# ears_v40.net
KiCad netlist of a schematic drawn in EAGLE
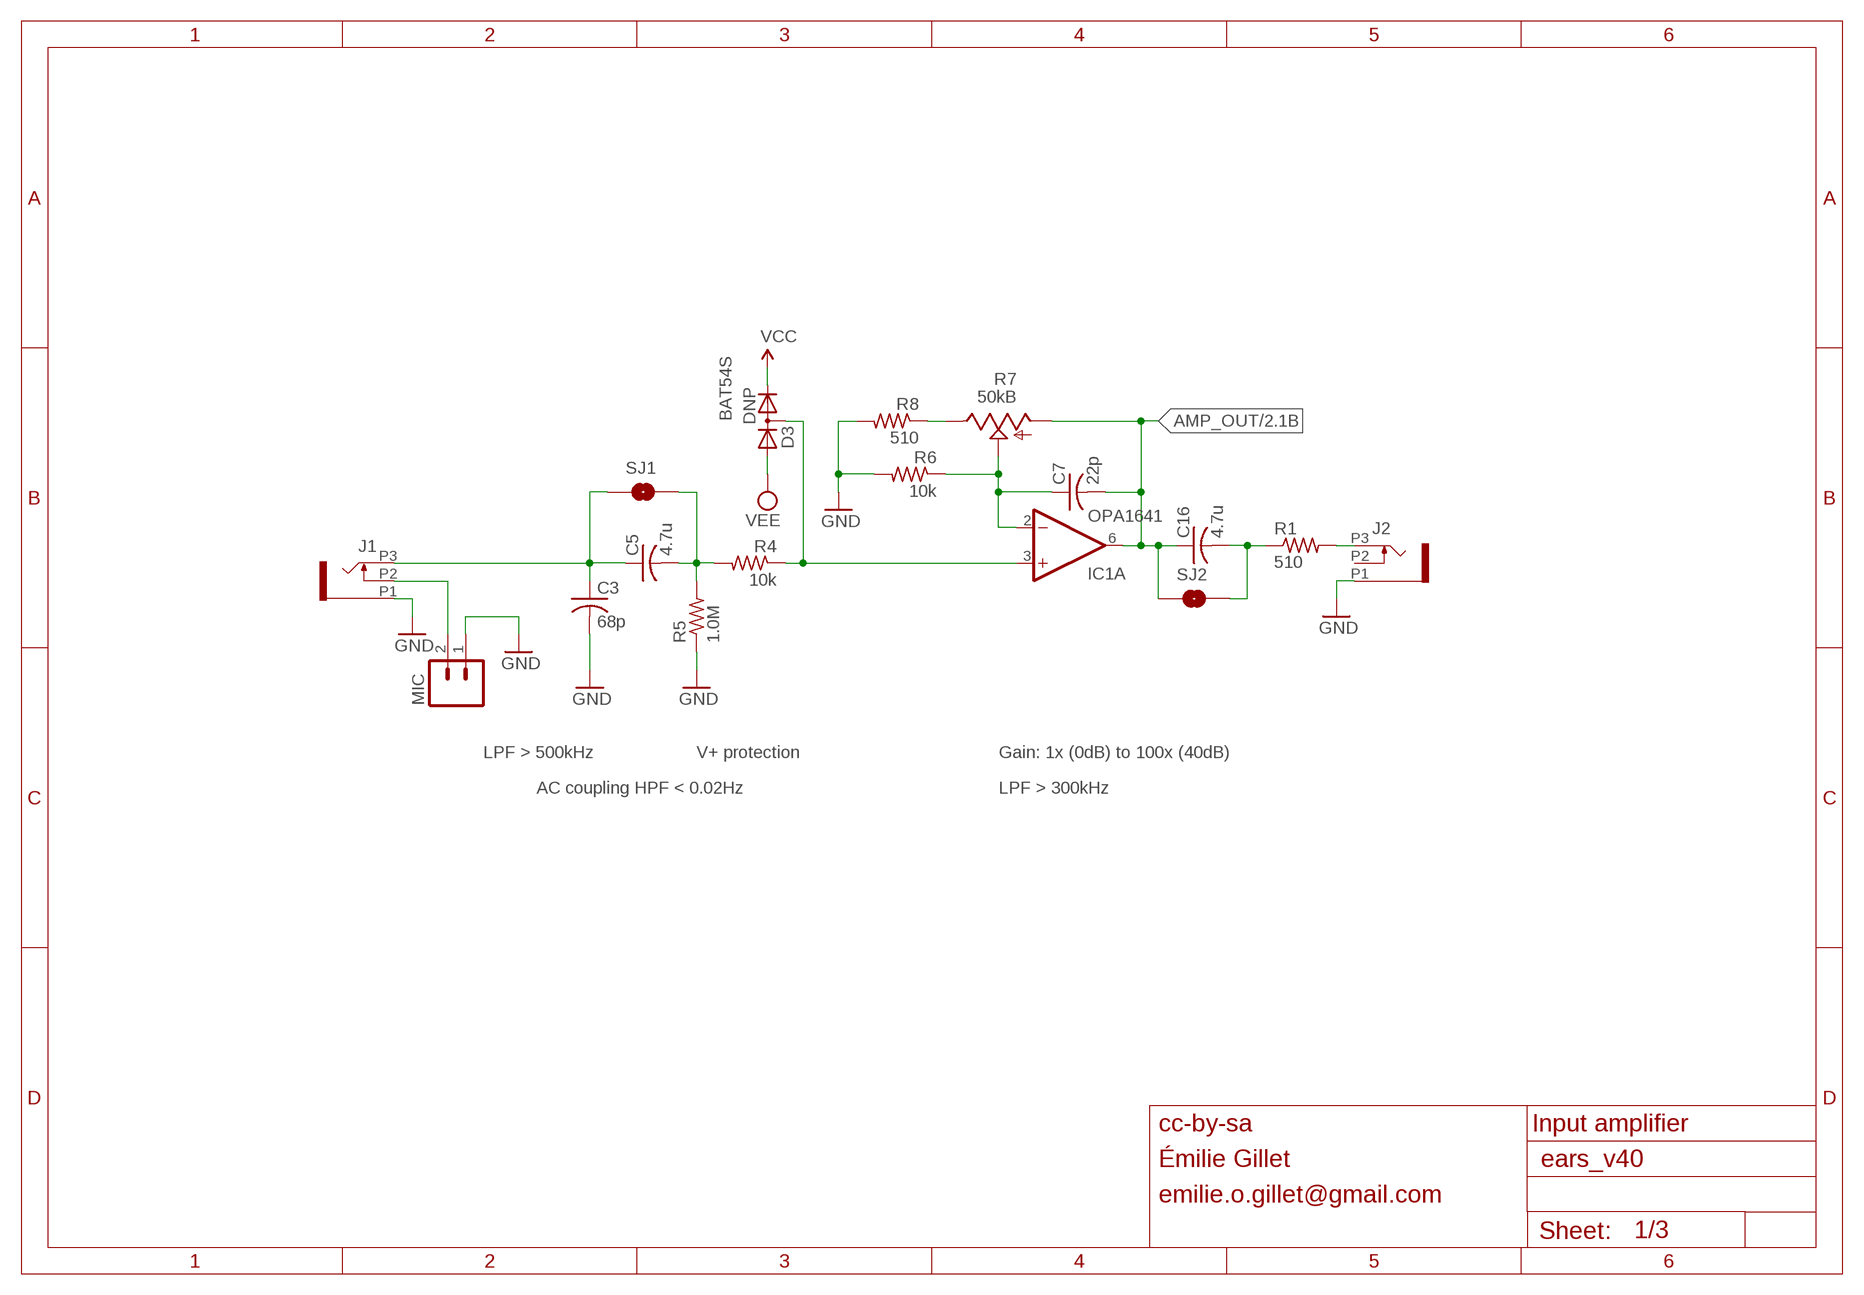
[diagram p0: schematic, sheet 1]
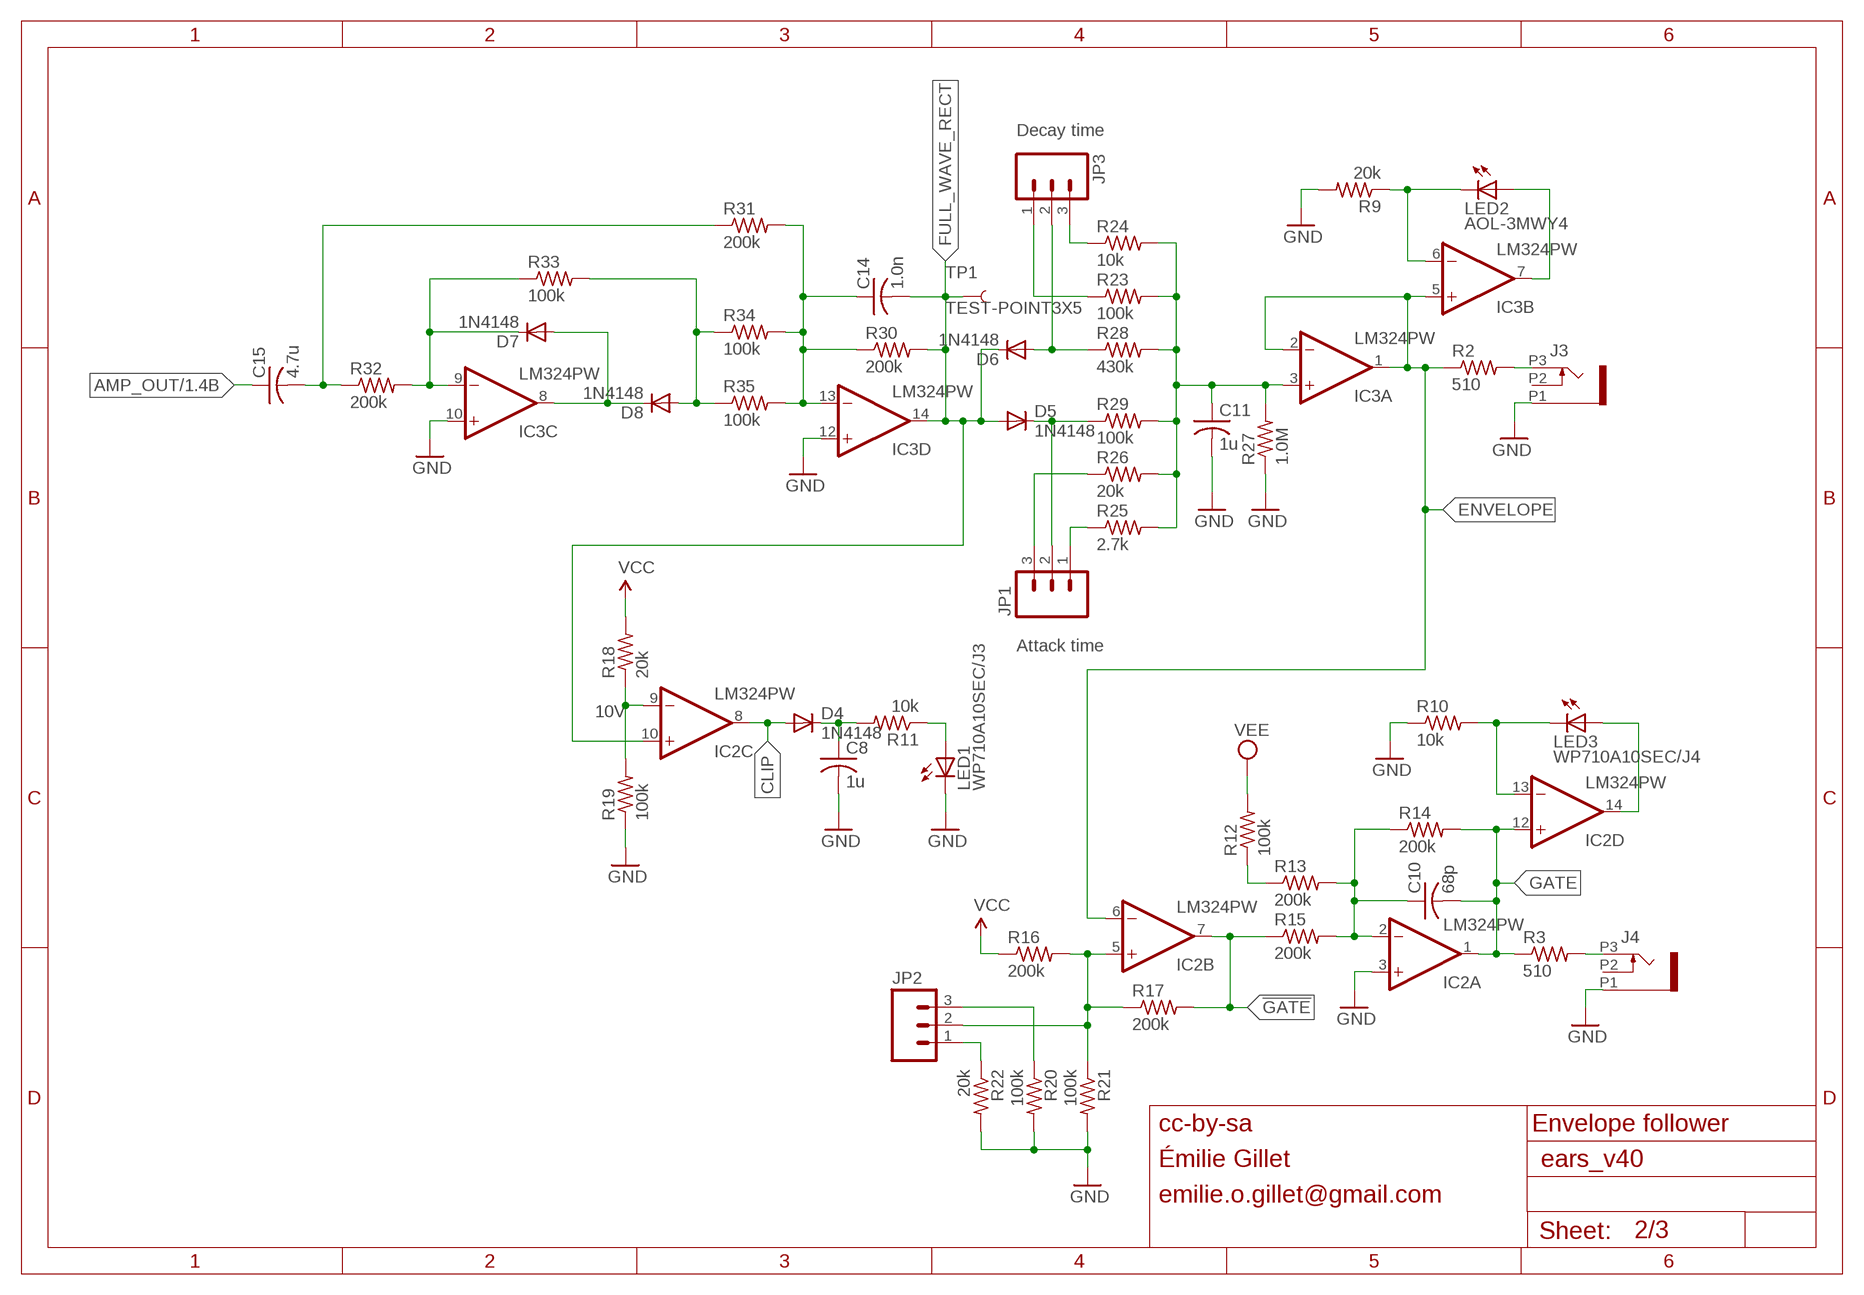
[diagram p1: schematic, sheet 2]
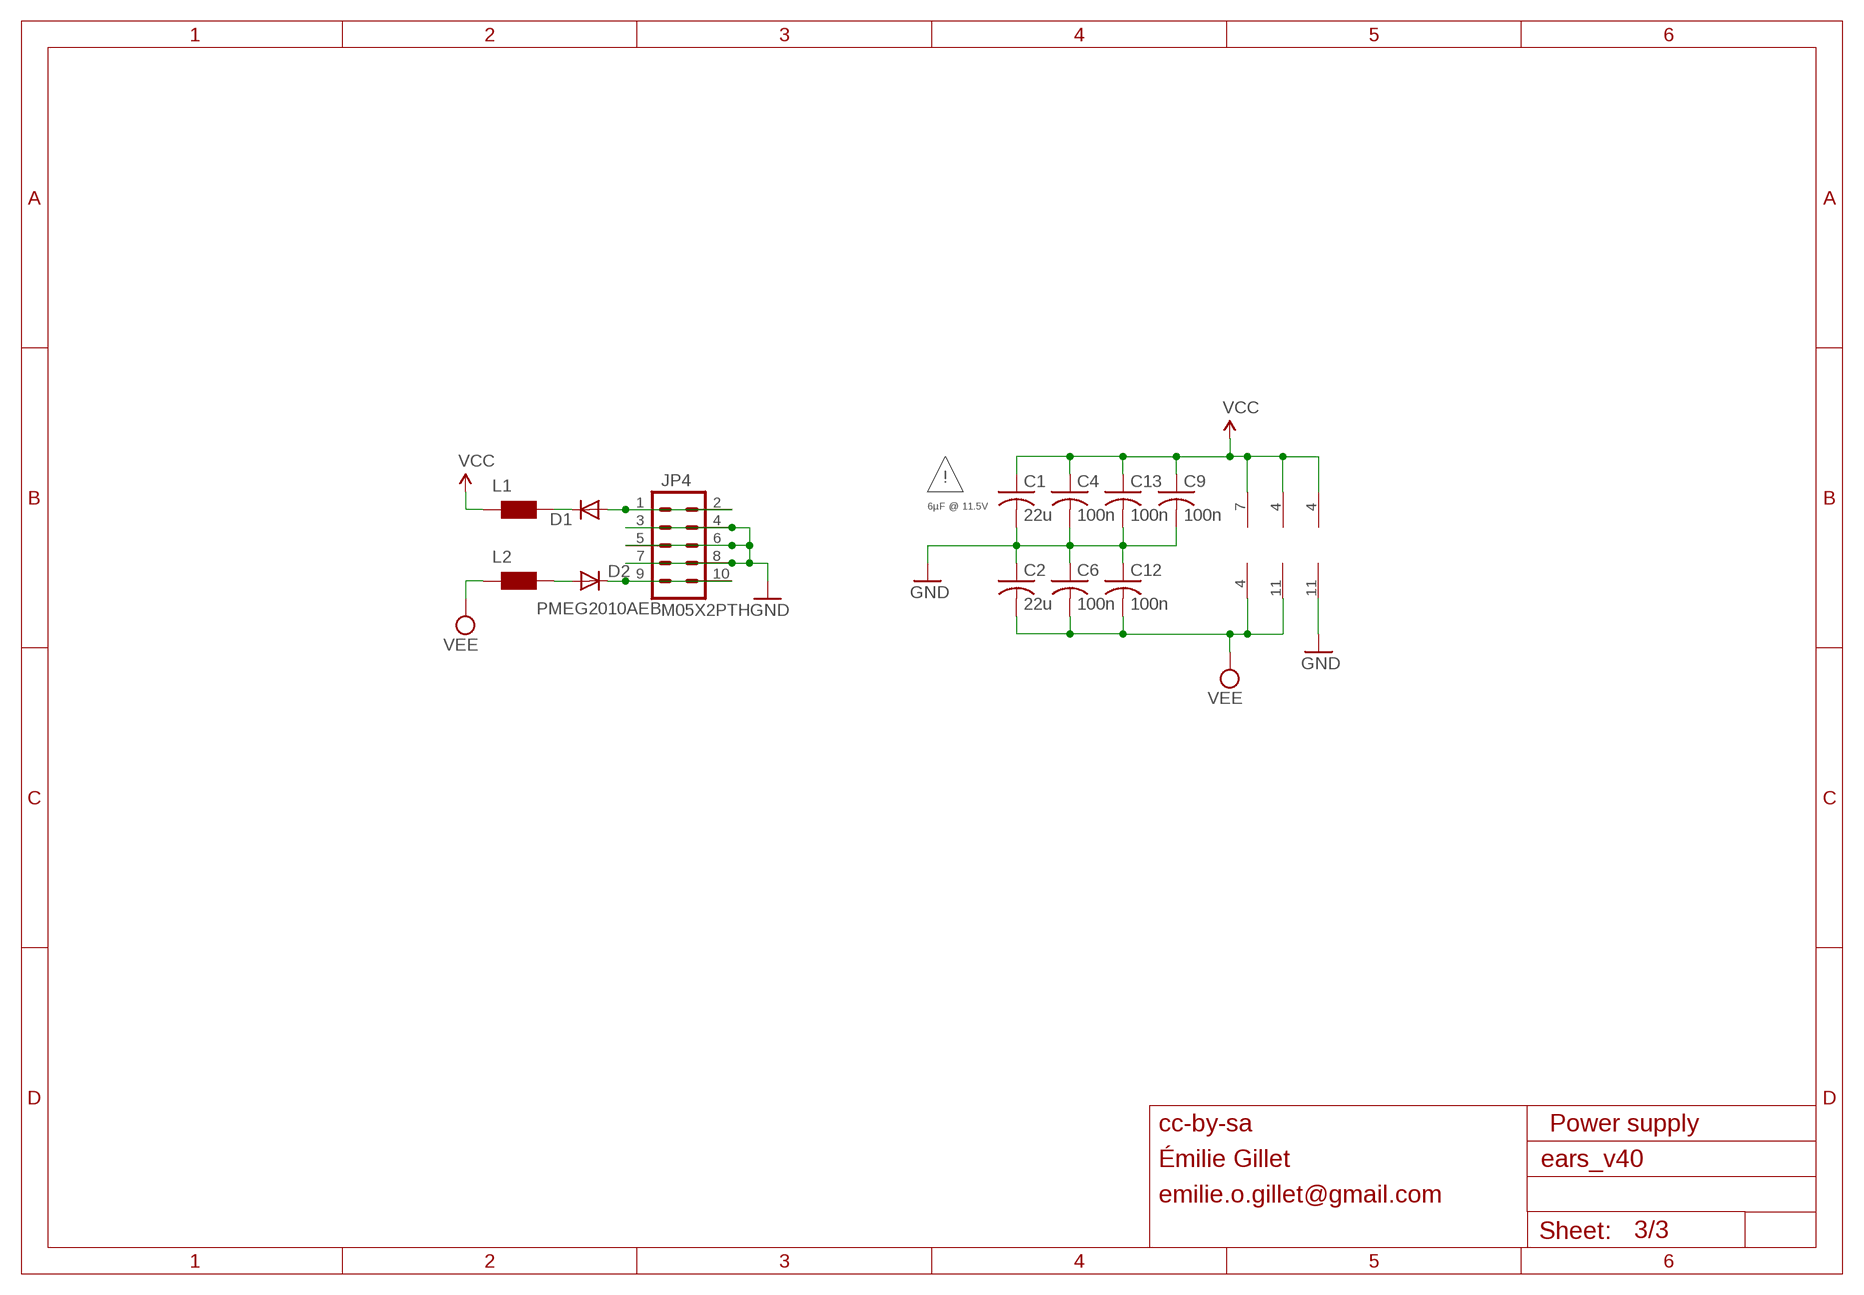
[diagram p2: schematic, sheet 3]

(export (version "E")
  (design (tool "Eeschema 10.0.6"))
  (components
    (comp (ref "C3")
      (value "68p")
      (footprint "eagle-import:C0402")
      (libsource (lib "eagle-import") (part "C-USC0402"))
    )
    (comp (ref "C5")
      (value "4.7u")
      (footprint "eagle-import:C0603")
      (libsource (lib "eagle-import") (part "C-USC0603"))
    )
    (comp (ref "C7")
      (value "22p")
      (footprint "eagle-import:C0402")
      (libsource (lib "eagle-import") (part "C-USC0402"))
    )
    (comp (ref "C16")
      (value "4.7u")
      (footprint "eagle-import:C0603")
      (libsource (lib "eagle-import") (part "C-USC0603"))
    )
    (comp (ref "D3")
      (value "DNP")
      (footprint "eagle-import:SOT23")
      (libsource (lib "eagle-import") (part "DIODE_2CACA-SOT23"))
    )
    (comp (ref "IC1")
      (value "OPA1641")
      (footprint "eagle-import:MSOP8")
      (libsource (lib "eagle-import") (part "OPA1641"))
    )
    (comp (ref "J1")
      (value "PJ301_THONKICONN6")
      (footprint "eagle-import:WQP_PJ_301M6")
      (libsource (lib "eagle-import") (part "PJ301_THONKICONN6"))
    )
    (comp (ref "J2")
      (value "PJ301_THONKICONN6")
      (footprint "eagle-import:WQP_PJ_301M6")
      (libsource (lib "eagle-import") (part "PJ301_THONKICONN6"))
    )
    (comp (ref "MIC")
      (value "M02TINY")
      (footprint "eagle-import:1X02_TINY")
      (libsource (lib "eagle-import") (part "M02TINY"))
    )
    (comp (ref "R1")
      (value "510")
      (footprint "eagle-import:R0402")
      (libsource (lib "eagle-import") (part "R-US_R0402"))
    )
    (comp (ref "R4")
      (value "10k")
      (footprint "eagle-import:R0402")
      (libsource (lib "eagle-import") (part "R-US_R0402"))
    )
    (comp (ref "R5")
      (value "1.0M")
      (footprint "eagle-import:R0402")
      (libsource (lib "eagle-import") (part "R-US_R0402"))
    )
    (comp (ref "R6")
      (value "10k")
      (footprint "eagle-import:R0402")
      (libsource (lib "eagle-import") (part "R-US_R0402"))
    )
    (comp (ref "R7")
      (value "50kB")
      (footprint "eagle-import:ALPS_POT_VERTICAL_PS")
      (libsource (lib "eagle-import") (part "POT_USVERTICAL_PS"))
    )
    (comp (ref "R8")
      (value "510")
      (footprint "eagle-import:R0402")
      (libsource (lib "eagle-import") (part "R-US_R0402"))
    )
    (comp (ref "SJ1")
      (value "SOLDERJUMPERNC")
      (footprint "eagle-import:SJ_2S")
      (libsource (lib "eagle-import") (part "SOLDERJUMPERNC"))
    )
    (comp (ref "SJ2")
      (value "SOLDERJUMPERNC")
      (footprint "eagle-import:SJ_2S")
      (libsource (lib "eagle-import") (part "SOLDERJUMPERNC"))
    )
    (comp (ref "C1")
      (value "22u")
      (footprint "eagle-import:C1206")
      (libsource (lib "eagle-import") (part "C-USC1206"))
    )
    (comp (ref "C2")
      (value "22u")
      (footprint "eagle-import:C1206")
      (libsource (lib "eagle-import") (part "C-USC1206"))
    )
    (comp (ref "C4")
      (value "100n")
      (footprint "eagle-import:C0402")
      (libsource (lib "eagle-import") (part "C-USC0402"))
    )
    (comp (ref "C6")
      (value "100n")
      (footprint "eagle-import:C0402")
      (libsource (lib "eagle-import") (part "C-USC0402"))
    )
    (comp (ref "C9")
      (value "100n")
      (footprint "eagle-import:C0402")
      (libsource (lib "eagle-import") (part "C-USC0402"))
    )
    (comp (ref "C12")
      (value "100n")
      (footprint "eagle-import:C0402")
      (libsource (lib "eagle-import") (part "C-USC0402"))
    )
    (comp (ref "C13")
      (value "100n")
      (footprint "eagle-import:C0402")
      (libsource (lib "eagle-import") (part "C-USC0402"))
    )
    (comp (ref "D1")
      (value "PMEG2010AEB")
      (footprint "eagle-import:SOD523")
      (libsource (lib "eagle-import") (part "DIODE-SOD523"))
    )
    (comp (ref "D2")
      (value "PMEG2010AEB")
      (footprint "eagle-import:SOD523")
      (libsource (lib "eagle-import") (part "DIODE-SOD523"))
    )
    (comp (ref "IC2")
      (value "LM324PW")
      (footprint "eagle-import:TSSOP14")
      (libsource (lib "eagle-import") (part "LM324PW"))
    )
    (comp (ref "IC3")
      (value "LM324PW")
      (footprint "eagle-import:TSSOP14")
      (libsource (lib "eagle-import") (part "LM324PW"))
    )
    (comp (ref "JP4")
      (value "M05X2PTH")
      (footprint "eagle-import:AVR_ICSP")
      (libsource (lib "eagle-import") (part "M05X2PTH"))
    )
    (comp (ref "L1")
      (value "WE-CBF_0603")
      (footprint "eagle-import:0603")
      (libsource (lib "eagle-import") (part "WE-CBF_0603"))
    )
    (comp (ref "L2")
      (value "WE-CBF_0603")
      (footprint "eagle-import:0603")
      (libsource (lib "eagle-import") (part "WE-CBF_0603"))
    )
    (comp (ref "C8")
      (value "1u")
      (footprint "eagle-import:C0402")
      (libsource (lib "eagle-import") (part "C-USC0402"))
    )
    (comp (ref "C10")
      (value "68p")
      (footprint "eagle-import:C0402")
      (libsource (lib "eagle-import") (part "C-USC0402"))
    )
    (comp (ref "C11")
      (value "1u")
      (footprint "eagle-import:C0402")
      (libsource (lib "eagle-import") (part "C-USC0402"))
    )
    (comp (ref "C14")
      (value "1.0n")
      (footprint "eagle-import:C0402")
      (libsource (lib "eagle-import") (part "C-USC0402"))
    )
    (comp (ref "C15")
      (value "4.7u")
      (footprint "eagle-import:C0603")
      (libsource (lib "eagle-import") (part "C-USC0603"))
    )
    (comp (ref "D4")
      (value "1N4148")
      (footprint "eagle-import:SOD523")
      (libsource (lib "eagle-import") (part "DIODE-SOD523"))
    )
    (comp (ref "D5")
      (value "1N4148")
      (footprint "eagle-import:SOD523")
      (libsource (lib "eagle-import") (part "DIODE-SOD523"))
    )
    (comp (ref "D6")
      (value "1N4148")
      (footprint "eagle-import:SOD523")
      (libsource (lib "eagle-import") (part "DIODE-SOD523"))
    )
    (comp (ref "D7")
      (value "1N4148")
      (footprint "eagle-import:SOD523")
      (libsource (lib "eagle-import") (part "DIODE-SOD523"))
    )
    (comp (ref "D8")
      (value "1N4148")
      (footprint "eagle-import:SOD523")
      (libsource (lib "eagle-import") (part "DIODE-SOD523"))
    )
    (comp (ref "J3")
      (value "PJ301_THONKICONN6")
      (footprint "eagle-import:WQP_PJ_301M6")
      (libsource (lib "eagle-import") (part "PJ301_THONKICONN6"))
    )
    (comp (ref "J4")
      (value "PJ301_THONKICONN6")
      (footprint "eagle-import:WQP_PJ_301M6")
      (libsource (lib "eagle-import") (part "PJ301_THONKICONN6"))
    )
    (comp (ref "JP1")
      (value "M03PTH")
      (footprint "eagle-import:1X03")
      (libsource (lib "eagle-import") (part "M03PTH"))
    )
    (comp (ref "JP2")
      (value "M03PTH")
      (footprint "eagle-import:1X03")
      (libsource (lib "eagle-import") (part "M03PTH"))
    )
    (comp (ref "JP3")
      (value "M03PTH")
      (footprint "eagle-import:1X03")
      (libsource (lib "eagle-import") (part "M03PTH"))
    )
    (comp (ref "LED1")
      (value "WP710A10SEC/J3")
      (footprint "eagle-import:LED3MM")
      (libsource (lib "eagle-import") (part "LED3MM"))
    )
    (comp (ref "LED2")
      (value "AOL-3MWY4")
      (footprint "eagle-import:LED3MM")
      (libsource (lib "eagle-import") (part "LED3MM"))
    )
    (comp (ref "LED3")
      (value "WP710A10SEC/J4")
      (footprint "eagle-import:LED3MM")
      (libsource (lib "eagle-import") (part "LED3MM"))
    )
    (comp (ref "R2")
      (value "510")
      (footprint "eagle-import:R0402")
      (libsource (lib "eagle-import") (part "R-US_R0402"))
    )
    (comp (ref "R3")
      (value "510")
      (footprint "eagle-import:R0402")
      (libsource (lib "eagle-import") (part "R-US_R0402"))
    )
    (comp (ref "R9")
      (value "20k")
      (footprint "eagle-import:R0402")
      (libsource (lib "eagle-import") (part "R-US_R0402"))
    )
    (comp (ref "R10")
      (value "10k")
      (footprint "eagle-import:R0402")
      (libsource (lib "eagle-import") (part "R-US_R0402"))
    )
    (comp (ref "R11")
      (value "10k")
      (footprint "eagle-import:R0402")
      (libsource (lib "eagle-import") (part "R-US_R0402"))
    )
    (comp (ref "R12")
      (value "100k")
      (footprint "eagle-import:R0402")
      (libsource (lib "eagle-import") (part "R-US_R0402"))
    )
    (comp (ref "R13")
      (value "200k")
      (footprint "eagle-import:R0402")
      (libsource (lib "eagle-import") (part "R-US_R0402"))
    )
    (comp (ref "R14")
      (value "200k")
      (footprint "eagle-import:R0402")
      (libsource (lib "eagle-import") (part "R-US_R0402"))
    )
    (comp (ref "R15")
      (value "200k")
      (footprint "eagle-import:R0402")
      (libsource (lib "eagle-import") (part "R-US_R0402"))
    )
    (comp (ref "R16")
      (value "200k")
      (footprint "eagle-import:R0402")
      (libsource (lib "eagle-import") (part "R-US_R0402"))
    )
    (comp (ref "R17")
      (value "200k")
      (footprint "eagle-import:R0402")
      (libsource (lib "eagle-import") (part "R-US_R0402"))
    )
    (comp (ref "R18")
      (value "20k")
      (footprint "eagle-import:R0402")
      (libsource (lib "eagle-import") (part "R-US_R0402"))
    )
    (comp (ref "R19")
      (value "100k")
      (footprint "eagle-import:R0402")
      (libsource (lib "eagle-import") (part "R-US_R0402"))
    )
    (comp (ref "R20")
      (value "100k")
      (footprint "eagle-import:R0402")
      (libsource (lib "eagle-import") (part "R-US_R0402"))
    )
    (comp (ref "R21")
      (value "100k")
      (footprint "eagle-import:R0402")
      (libsource (lib "eagle-import") (part "R-US_R0402"))
    )
    (comp (ref "R22")
      (value "20k")
      (footprint "eagle-import:R0402")
      (libsource (lib "eagle-import") (part "R-US_R0402"))
    )
    (comp (ref "R23")
      (value "100k")
      (footprint "eagle-import:R0402")
      (libsource (lib "eagle-import") (part "R-US_R0402"))
    )
    (comp (ref "R24")
      (value "10k")
      (footprint "eagle-import:R0402")
      (libsource (lib "eagle-import") (part "R-US_R0402"))
    )
    (comp (ref "R25")
      (value "2.7k")
      (footprint "eagle-import:R0402")
      (libsource (lib "eagle-import") (part "R-US_R0402"))
    )
    (comp (ref "R26")
      (value "20k")
      (footprint "eagle-import:R0402")
      (libsource (lib "eagle-import") (part "R-US_R0402"))
    )
    (comp (ref "R27")
      (value "1.0M")
      (footprint "eagle-import:R0402")
      (libsource (lib "eagle-import") (part "R-US_R0402"))
    )
    (comp (ref "R28")
      (value "430k")
      (footprint "eagle-import:R0402")
      (libsource (lib "eagle-import") (part "R-US_R0402"))
    )
    (comp (ref "R29")
      (value "100k")
      (footprint "eagle-import:R0402")
      (libsource (lib "eagle-import") (part "R-US_R0402"))
    )
    (comp (ref "R30")
      (value "200k")
      (footprint "eagle-import:R0402")
      (libsource (lib "eagle-import") (part "R-US_R0402"))
    )
    (comp (ref "R31")
      (value "200k")
      (footprint "eagle-import:R0402")
      (libsource (lib "eagle-import") (part "R-US_R0402"))
    )
    (comp (ref "R32")
      (value "200k")
      (footprint "eagle-import:R0402")
      (libsource (lib "eagle-import") (part "R-US_R0402"))
    )
    (comp (ref "R33")
      (value "100k")
      (footprint "eagle-import:R0402")
      (libsource (lib "eagle-import") (part "R-US_R0402"))
    )
    (comp (ref "R34")
      (value "100k")
      (footprint "eagle-import:R0402")
      (libsource (lib "eagle-import") (part "R-US_R0402"))
    )
    (comp (ref "R35")
      (value "100k")
      (footprint "eagle-import:R0402")
      (libsource (lib "eagle-import") (part "R-US_R0402"))
    )
    (comp (ref "TP1")
      (value "TEST-POINT3X5")
      (footprint "eagle-import:PAD.03X.05")
      (libsource (lib "eagle-import") (part "TEST-POINT3X5"))
    )
  )
  (nets
    (net (code "1") (name "AMP_OUT") (class "Default")
      (node (ref "C15") (pin "1") (pinfunction "1_1") (pintype "passive"))
      (node (ref "C16") (pin "1") (pinfunction "1_1") (pintype "passive"))
      (node (ref "C7") (pin "2") (pinfunction "2_2") (pintype "passive"))
      (node (ref "IC1") (pin "6") (pinfunction "OUT_6") (pintype "output"))
      (node (ref "R7") (pin "P$3") (pinfunction "A_P$3") (pintype "passive"))
      (node (ref "SJ2") (pin "1") (pinfunction "1_1") (pintype "passive"))
    )
    (net (code "2") (name "CLIP") (class "Default")
      (node (ref "D4") (pin "A") (pinfunction "A_A") (pintype "passive"))
      (node (ref "IC2") (pin "8") (pinfunction "OUT_8") (pintype "output"))
    )
    (net (code "3") (name "ENVELOPE") (class "Default")
      (node (ref "IC2") (pin "6") (pinfunction "-IN_6") (pintype "input"))
      (node (ref "IC3") (pin "1") (pinfunction "OUT_1") (pintype "output"))
      (node (ref "IC3") (pin "2") (pinfunction "-IN_2") (pintype "input"))
      (node (ref "IC3") (pin "5") (pinfunction "+IN_5") (pintype "input"))
      (node (ref "R2") (pin "1") (pinfunction "1_1") (pintype "passive"))
    )
    (net (code "4") (name "FULL_WAVE_RECT") (class "Default")
      (node (ref "C14") (pin "2") (pinfunction "2_2") (pintype "passive"))
      (node (ref "D5") (pin "A") (pinfunction "A_A") (pintype "passive"))
      (node (ref "D6") (pin "C") (pinfunction "C_C") (pintype "passive"))
      (node (ref "IC2") (pin "10") (pinfunction "+IN_10") (pintype "input"))
      (node (ref "IC3") (pin "14") (pinfunction "OUT_14") (pintype "output"))
      (node (ref "R30") (pin "2") (pinfunction "2_2") (pintype "passive"))
      (node (ref "TP1") (pin "P$1") (pinfunction "1_P$1") (pintype "bidirectional"))
    )
    (net (code "5") (name "GATE") (class "Default")
      (node (ref "C10") (pin "2") (pinfunction "2_2") (pintype "passive"))
      (node (ref "IC2") (pin "1") (pinfunction "OUT_1") (pintype "output"))
      (node (ref "IC2") (pin "12") (pinfunction "+IN_12") (pintype "input"))
      (node (ref "R14") (pin "2") (pinfunction "2_2") (pintype "passive"))
      (node (ref "R3") (pin "1") (pinfunction "1_1") (pintype "passive"))
    )
    (net (code "6") (name "GND") (class "Default")
      (node (ref "C1") (pin "2") (pinfunction "2_2") (pintype "passive"))
      (node (ref "C11") (pin "2") (pinfunction "2_2") (pintype "passive"))
      (node (ref "C12") (pin "1") (pinfunction "1_1") (pintype "passive"))
      (node (ref "C13") (pin "2") (pinfunction "2_2") (pintype "passive"))
      (node (ref "C2") (pin "1") (pinfunction "1_1") (pintype "passive"))
      (node (ref "C3") (pin "2") (pinfunction "2_2") (pintype "passive"))
      (node (ref "C4") (pin "2") (pinfunction "2_2") (pintype "passive"))
      (node (ref "C6") (pin "1") (pinfunction "1_1") (pintype "passive"))
      (node (ref "C8") (pin "2") (pinfunction "2_2") (pintype "passive"))
      (node (ref "C9") (pin "2") (pinfunction "2_2") (pintype "passive"))
      (node (ref "IC2") (pin "11") (pinfunction "V-_11") (pintype "power_in"))
      (node (ref "IC2") (pin "3") (pinfunction "+IN_3") (pintype "input"))
      (node (ref "IC3") (pin "10") (pinfunction "+IN_10") (pintype "input"))
      (node (ref "IC3") (pin "12") (pinfunction "+IN_12") (pintype "input"))
      (node (ref "J1") (pin "P1") (pinfunction "1_P1") (pintype "passive"))
      (node (ref "J2") (pin "P1") (pinfunction "1_P1") (pintype "passive"))
      (node (ref "J3") (pin "P1") (pinfunction "1_P1") (pintype "passive"))
      (node (ref "J4") (pin "P1") (pinfunction "1_P1") (pintype "passive"))
      (node (ref "JP4") (pin "3") (pinfunction "3_3") (pintype "passive"))
      (node (ref "JP4") (pin "4") (pinfunction "4_4") (pintype "passive"))
      (node (ref "JP4") (pin "5") (pinfunction "5_5") (pintype "passive"))
      (node (ref "JP4") (pin "6") (pinfunction "6_6") (pintype "passive"))
      (node (ref "JP4") (pin "7") (pinfunction "7_7") (pintype "passive"))
      (node (ref "JP4") (pin "8") (pinfunction "8_8") (pintype "passive"))
      (node (ref "LED1") (pin "K") (pinfunction "C_K") (pintype "passive"))
      (node (ref "MIC") (pin "1") (pinfunction "1_1") (pintype "passive"))
      (node (ref "R10") (pin "1") (pinfunction "1_1") (pintype "passive"))
      (node (ref "R19") (pin "1") (pinfunction "1_1") (pintype "passive"))
      (node (ref "R20") (pin "2") (pinfunction "2_2") (pintype "passive"))
      (node (ref "R21") (pin "2") (pinfunction "2_2") (pintype "passive"))
      (node (ref "R22") (pin "2") (pinfunction "2_2") (pintype "passive"))
      (node (ref "R27") (pin "1") (pinfunction "1_1") (pintype "passive"))
      (node (ref "R5") (pin "1") (pinfunction "1_1") (pintype "passive"))
      (node (ref "R6") (pin "2") (pinfunction "2_2") (pintype "passive"))
      (node (ref "R8") (pin "2") (pinfunction "2_2") (pintype "passive"))
      (node (ref "R9") (pin "2") (pinfunction "2_2") (pintype "passive"))
    )
    (net (code "7") (name "Net-(C5-Pad2)") (class "Default")
      (node (ref "C5") (pin "2") (pinfunction "2_2") (pintype "passive"))
      (node (ref "R4") (pin "2") (pinfunction "2_2") (pintype "passive"))
      (node (ref "R5") (pin "2") (pinfunction "2_2") (pintype "passive"))
      (node (ref "SJ1") (pin "2") (pinfunction "2_2") (pintype "passive"))
    )
    (net (code "8") (name "Net-(C8-Pad1)") (class "Default")
      (node (ref "C8") (pin "1") (pinfunction "1_1") (pintype "passive"))
      (node (ref "D4") (pin "C") (pinfunction "C_C") (pintype "passive"))
      (node (ref "R11") (pin "2") (pinfunction "2_2") (pintype "passive"))
    )
    (net (code "9") (name "Net-(C15-Pad2)") (class "Default")
      (node (ref "C15") (pin "2") (pinfunction "2_2") (pintype "passive"))
      (node (ref "R31") (pin "1") (pinfunction "1_1") (pintype "passive"))
      (node (ref "R32") (pin "1") (pinfunction "1_1") (pintype "passive"))
    )
    (net (code "10") (name "Net-(C16-Pad2)") (class "Default")
      (node (ref "C16") (pin "2") (pinfunction "2_2") (pintype "passive"))
      (node (ref "R1") (pin "1") (pinfunction "1_1") (pintype "passive"))
      (node (ref "SJ2") (pin "2") (pinfunction "2_2") (pintype "passive"))
    )
    (net (code "11") (name "Net-(D1-PadA)") (class "Default")
      (node (ref "D1") (pin "A") (pinfunction "A_A") (pintype "passive"))
      (node (ref "JP4") (pin "1") (pinfunction "1_1") (pintype "passive"))
      (node (ref "JP4") (pin "2") (pinfunction "2_2") (pintype "passive"))
    )
    (net (code "12") (name "Net-(D1-PadC)") (class "Default")
      (node (ref "D1") (pin "C") (pinfunction "C_C") (pintype "passive"))
      (node (ref "L1") (pin "2") (pinfunction "2_2") (pintype "passive"))
    )
    (net (code "13") (name "Net-(D2-PadA)") (class "Default")
      (node (ref "D2") (pin "A") (pinfunction "A_A") (pintype "passive"))
      (node (ref "L2") (pin "2") (pinfunction "2_2") (pintype "passive"))
    )
    (net (code "14") (name "Net-(D2-PadC)") (class "Default")
      (node (ref "D2") (pin "C") (pinfunction "C_C") (pintype "passive"))
      (node (ref "JP4") (pin "10") (pinfunction "10_10") (pintype "passive"))
      (node (ref "JP4") (pin "9") (pinfunction "9_9") (pintype "passive"))
    )
    (net (code "15") (name "Net-(D3-AC)") (class "Default")
      (node (ref "D3") (pin "3") (pinfunction "AC_3") (pintype "passive"))
      (node (ref "IC1") (pin "3") (pinfunction "+IN_3") (pintype "input"))
      (node (ref "R4") (pin "1") (pinfunction "1_1") (pintype "passive"))
    )
    (net (code "16") (name "Net-(D5-PadC)") (class "Default")
      (node (ref "D5") (pin "C") (pinfunction "C_C") (pintype "passive"))
      (node (ref "JP1") (pin "2") (pinfunction "2_2") (pintype "passive"))
      (node (ref "R29") (pin "1") (pinfunction "1_1") (pintype "passive"))
    )
    (net (code "17") (name "Net-(D6-PadA)") (class "Default")
      (node (ref "D6") (pin "A") (pinfunction "A_A") (pintype "passive"))
      (node (ref "JP3") (pin "2") (pinfunction "2_2") (pintype "passive"))
      (node (ref "R28") (pin "1") (pinfunction "1_1") (pintype "passive"))
    )
    (net (code "18") (name "Net-(D8-PadA)") (class "Default")
      (node (ref "D8") (pin "A") (pinfunction "A_A") (pintype "passive"))
      (node (ref "R33") (pin "2") (pinfunction "2_2") (pintype "passive"))
      (node (ref "R34") (pin "1") (pinfunction "1_1") (pintype "passive"))
      (node (ref "R35") (pin "1") (pinfunction "1_1") (pintype "passive"))
    )
    (net (code "19") (name "Net-(IC1A--IN)") (class "Default")
      (node (ref "C7") (pin "1") (pinfunction "1_1") (pintype "passive"))
      (node (ref "IC1") (pin "2") (pinfunction "-IN_2") (pintype "input"))
      (node (ref "R6") (pin "1") (pinfunction "1_1") (pintype "passive"))
      (node (ref "R7") (pin "P$2") (pinfunction "S_P$2") (pintype "passive"))
    )
    (net (code "20") (name "Net-(IC2A--IN)") (class "Default")
      (node (ref "C10") (pin "1") (pinfunction "1_1") (pintype "passive"))
      (node (ref "IC2") (pin "2") (pinfunction "-IN_2") (pintype "input"))
      (node (ref "R13") (pin "2") (pinfunction "2_2") (pintype "passive"))
      (node (ref "R14") (pin "1") (pinfunction "1_1") (pintype "passive"))
      (node (ref "R15") (pin "2") (pinfunction "2_2") (pintype "passive"))
    )
    (net (code "21") (name "Net-(IC2B-+IN)") (class "Default")
      (node (ref "IC2") (pin "5") (pinfunction "+IN_5") (pintype "input"))
      (node (ref "JP2") (pin "2") (pinfunction "2_2") (pintype "passive"))
      (node (ref "R16") (pin "2") (pinfunction "2_2") (pintype "passive"))
      (node (ref "R17") (pin "1") (pinfunction "1_1") (pintype "passive"))
      (node (ref "R21") (pin "1") (pinfunction "1_1") (pintype "passive"))
    )
    (net (code "22") (name "Net-(IC2C--IN)") (class "Default")
      (node (ref "IC2") (pin "9") (pinfunction "-IN_9") (pintype "input"))
      (node (ref "R18") (pin "1") (pinfunction "1_1") (pintype "passive"))
      (node (ref "R19") (pin "2") (pinfunction "2_2") (pintype "passive"))
    )
    (net (code "23") (name "Net-(IC2D--IN)") (class "Default")
      (node (ref "IC2") (pin "13") (pinfunction "-IN_13") (pintype "input"))
      (node (ref "LED3") (pin "K") (pinfunction "C_K") (pintype "passive"))
      (node (ref "R10") (pin "2") (pinfunction "2_2") (pintype "passive"))
    )
    (net (code "24") (name "Net-(IC2D-OUT)") (class "Default")
      (node (ref "IC2") (pin "14") (pinfunction "OUT_14") (pintype "output"))
      (node (ref "LED3") (pin "A") (pinfunction "A_A") (pintype "passive"))
    )
    (net (code "25") (name "Net-(IC3A-+IN)") (class "Default")
      (node (ref "C11") (pin "1") (pinfunction "1_1") (pintype "passive"))
      (node (ref "IC3") (pin "3") (pinfunction "+IN_3") (pintype "input"))
      (node (ref "R23") (pin "2") (pinfunction "2_2") (pintype "passive"))
      (node (ref "R24") (pin "2") (pinfunction "2_2") (pintype "passive"))
      (node (ref "R25") (pin "2") (pinfunction "2_2") (pintype "passive"))
      (node (ref "R26") (pin "2") (pinfunction "2_2") (pintype "passive"))
      (node (ref "R27") (pin "2") (pinfunction "2_2") (pintype "passive"))
      (node (ref "R28") (pin "2") (pinfunction "2_2") (pintype "passive"))
      (node (ref "R29") (pin "2") (pinfunction "2_2") (pintype "passive"))
    )
    (net (code "26") (name "Net-(IC3B--IN)") (class "Default")
      (node (ref "IC3") (pin "6") (pinfunction "-IN_6") (pintype "input"))
      (node (ref "LED2") (pin "K") (pinfunction "C_K") (pintype "passive"))
      (node (ref "R9") (pin "1") (pinfunction "1_1") (pintype "passive"))
    )
    (net (code "27") (name "Net-(IC3B-OUT)") (class "Default")
      (node (ref "IC3") (pin "7") (pinfunction "OUT_7") (pintype "output"))
      (node (ref "LED2") (pin "A") (pinfunction "A_A") (pintype "passive"))
    )
    (net (code "28") (name "Net-(IC3C--IN)") (class "Default")
      (node (ref "D7") (pin "C") (pinfunction "C_C") (pintype "passive"))
      (node (ref "IC3") (pin "9") (pinfunction "-IN_9") (pintype "input"))
      (node (ref "R32") (pin "2") (pinfunction "2_2") (pintype "passive"))
      (node (ref "R33") (pin "1") (pinfunction "1_1") (pintype "passive"))
    )
    (net (code "29") (name "Net-(IC3C-OUT)") (class "Default")
      (node (ref "D7") (pin "A") (pinfunction "A_A") (pintype "passive"))
      (node (ref "D8") (pin "C") (pinfunction "C_C") (pintype "passive"))
      (node (ref "IC3") (pin "8") (pinfunction "OUT_8") (pintype "output"))
    )
    (net (code "30") (name "Net-(IC3D--IN)") (class "Default")
      (node (ref "C14") (pin "1") (pinfunction "1_1") (pintype "passive"))
      (node (ref "IC3") (pin "13") (pinfunction "-IN_13") (pintype "input"))
      (node (ref "R30") (pin "1") (pinfunction "1_1") (pintype "passive"))
      (node (ref "R31") (pin "2") (pinfunction "2_2") (pintype "passive"))
      (node (ref "R34") (pin "2") (pinfunction "2_2") (pintype "passive"))
      (node (ref "R35") (pin "2") (pinfunction "2_2") (pintype "passive"))
    )
    (net (code "31") (name "Net-(J1-2)") (class "Default")
      (node (ref "J1") (pin "P2") (pinfunction "2_P2") (pintype "passive"))
      (node (ref "MIC") (pin "2") (pinfunction "2_2") (pintype "passive"))
    )
    (net (code "32") (name "Net-(J1-3)") (class "Default")
      (node (ref "C3") (pin "1") (pinfunction "1_1") (pintype "passive"))
      (node (ref "C5") (pin "1") (pinfunction "1_1") (pintype "passive"))
      (node (ref "J1") (pin "P3") (pinfunction "3_P3") (pintype "passive"))
      (node (ref "SJ1") (pin "1") (pinfunction "1_1") (pintype "passive"))
    )
    (net (code "33") (name "Net-(J2-3)") (class "Default")
      (node (ref "J2") (pin "P3") (pinfunction "3_P3") (pintype "passive"))
      (node (ref "R1") (pin "2") (pinfunction "2_2") (pintype "passive"))
    )
    (net (code "34") (name "Net-(J3-3)") (class "Default")
      (node (ref "J3") (pin "P3") (pinfunction "3_P3") (pintype "passive"))
      (node (ref "R2") (pin "2") (pinfunction "2_2") (pintype "passive"))
    )
    (net (code "35") (name "Net-(J4-3)") (class "Default")
      (node (ref "J4") (pin "P3") (pinfunction "3_P3") (pintype "passive"))
      (node (ref "R3") (pin "2") (pinfunction "2_2") (pintype "passive"))
    )
    (net (code "36") (name "Net-(JP1-Pad1)") (class "Default")
      (node (ref "JP1") (pin "1") (pinfunction "1_1") (pintype "passive"))
      (node (ref "R25") (pin "1") (pinfunction "1_1") (pintype "passive"))
    )
    (net (code "37") (name "Net-(JP1-Pad3)") (class "Default")
      (node (ref "JP1") (pin "3") (pinfunction "3_3") (pintype "passive"))
      (node (ref "R26") (pin "1") (pinfunction "1_1") (pintype "passive"))
    )
    (net (code "38") (name "Net-(JP2-Pad1)") (class "Default")
      (node (ref "JP2") (pin "1") (pinfunction "1_1") (pintype "passive"))
      (node (ref "R22") (pin "1") (pinfunction "1_1") (pintype "passive"))
    )
    (net (code "39") (name "Net-(JP2-Pad3)") (class "Default")
      (node (ref "JP2") (pin "3") (pinfunction "3_3") (pintype "passive"))
      (node (ref "R20") (pin "1") (pinfunction "1_1") (pintype "passive"))
    )
    (net (code "40") (name "Net-(JP3-Pad1)") (class "Default")
      (node (ref "JP3") (pin "1") (pinfunction "1_1") (pintype "passive"))
      (node (ref "R23") (pin "1") (pinfunction "1_1") (pintype "passive"))
    )
    (net (code "41") (name "Net-(JP3-Pad3)") (class "Default")
      (node (ref "JP3") (pin "3") (pinfunction "3_3") (pintype "passive"))
      (node (ref "R24") (pin "1") (pinfunction "1_1") (pintype "passive"))
    )
    (net (code "42") (name "Net-(LED1-PadA)") (class "Default")
      (node (ref "LED1") (pin "A") (pinfunction "A_A") (pintype "passive"))
      (node (ref "R11") (pin "1") (pinfunction "1_1") (pintype "passive"))
    )
    (net (code "43") (name "Net-(R7-E)") (class "Default")
      (node (ref "R7") (pin "P$1") (pinfunction "E_P$1") (pintype "passive"))
      (node (ref "R8") (pin "1") (pinfunction "1_1") (pintype "passive"))
    )
    (net (code "44") (name "Net-(R12-Pad1)") (class "Default")
      (node (ref "R12") (pin "1") (pinfunction "1_1") (pintype "passive"))
      (node (ref "R13") (pin "1") (pinfunction "1_1") (pintype "passive"))
    )
    (net (code "45") (name "VCC") (class "Default")
      (node (ref "C1") (pin "1") (pinfunction "1_1") (pintype "passive"))
      (node (ref "C13") (pin "1") (pinfunction "1_1") (pintype "passive"))
      (node (ref "C4") (pin "1") (pinfunction "1_1") (pintype "passive"))
      (node (ref "C9") (pin "1") (pinfunction "1_1") (pintype "passive"))
      (node (ref "D3") (pin "2") (pinfunction "C_2") (pintype "passive"))
      (node (ref "IC1") (pin "7") (pinfunction "V+_7") (pintype "power_in"))
      (node (ref "IC2") (pin "4") (pinfunction "V+_4") (pintype "power_in"))
      (node (ref "IC3") (pin "4") (pinfunction "V+_4") (pintype "power_in"))
      (node (ref "L1") (pin "1") (pinfunction "1_1") (pintype "passive"))
      (node (ref "R16") (pin "1") (pinfunction "1_1") (pintype "passive"))
      (node (ref "R18") (pin "2") (pinfunction "2_2") (pintype "passive"))
    )
    (net (code "46") (name "VEE") (class "Default")
      (node (ref "C12") (pin "2") (pinfunction "2_2") (pintype "passive"))
      (node (ref "C2") (pin "2") (pinfunction "2_2") (pintype "passive"))
      (node (ref "C6") (pin "2") (pinfunction "2_2") (pintype "passive"))
      (node (ref "D3") (pin "1") (pinfunction "A_1") (pintype "passive"))
      (node (ref "IC1") (pin "4") (pinfunction "V-_4") (pintype "power_in"))
      (node (ref "IC3") (pin "11") (pinfunction "V-_11") (pintype "power_in"))
      (node (ref "L2") (pin "1") (pinfunction "1_1") (pintype "passive"))
      (node (ref "R12") (pin "2") (pinfunction "2_2") (pintype "passive"))
    )
    (net (code "47") (name "unconnected-(J2-2-PadP2)") (class "Default")
      (node (ref "J2") (pin "P2") (pinfunction "2_P2") (pintype "passive"))
    )
    (net (code "48") (name "unconnected-(J3-2-PadP2)") (class "Default")
      (node (ref "J3") (pin "P2") (pinfunction "2_P2") (pintype "passive"))
    )
    (net (code "49") (name "unconnected-(J4-2-PadP2)") (class "Default")
      (node (ref "J4") (pin "P2") (pinfunction "2_P2") (pintype "passive"))
    )
    (net (code "50") (name "~{GATE}") (class "Default")
      (node (ref "IC2") (pin "7") (pinfunction "OUT_7") (pintype "output"))
      (node (ref "R15") (pin "1") (pinfunction "1_1") (pintype "passive"))
      (node (ref "R17") (pin "2") (pinfunction "2_2") (pintype "passive"))
    )
  )
)
